# VenturinoDrive.net
KiCad netlist of a schematic drawn in EAGLE
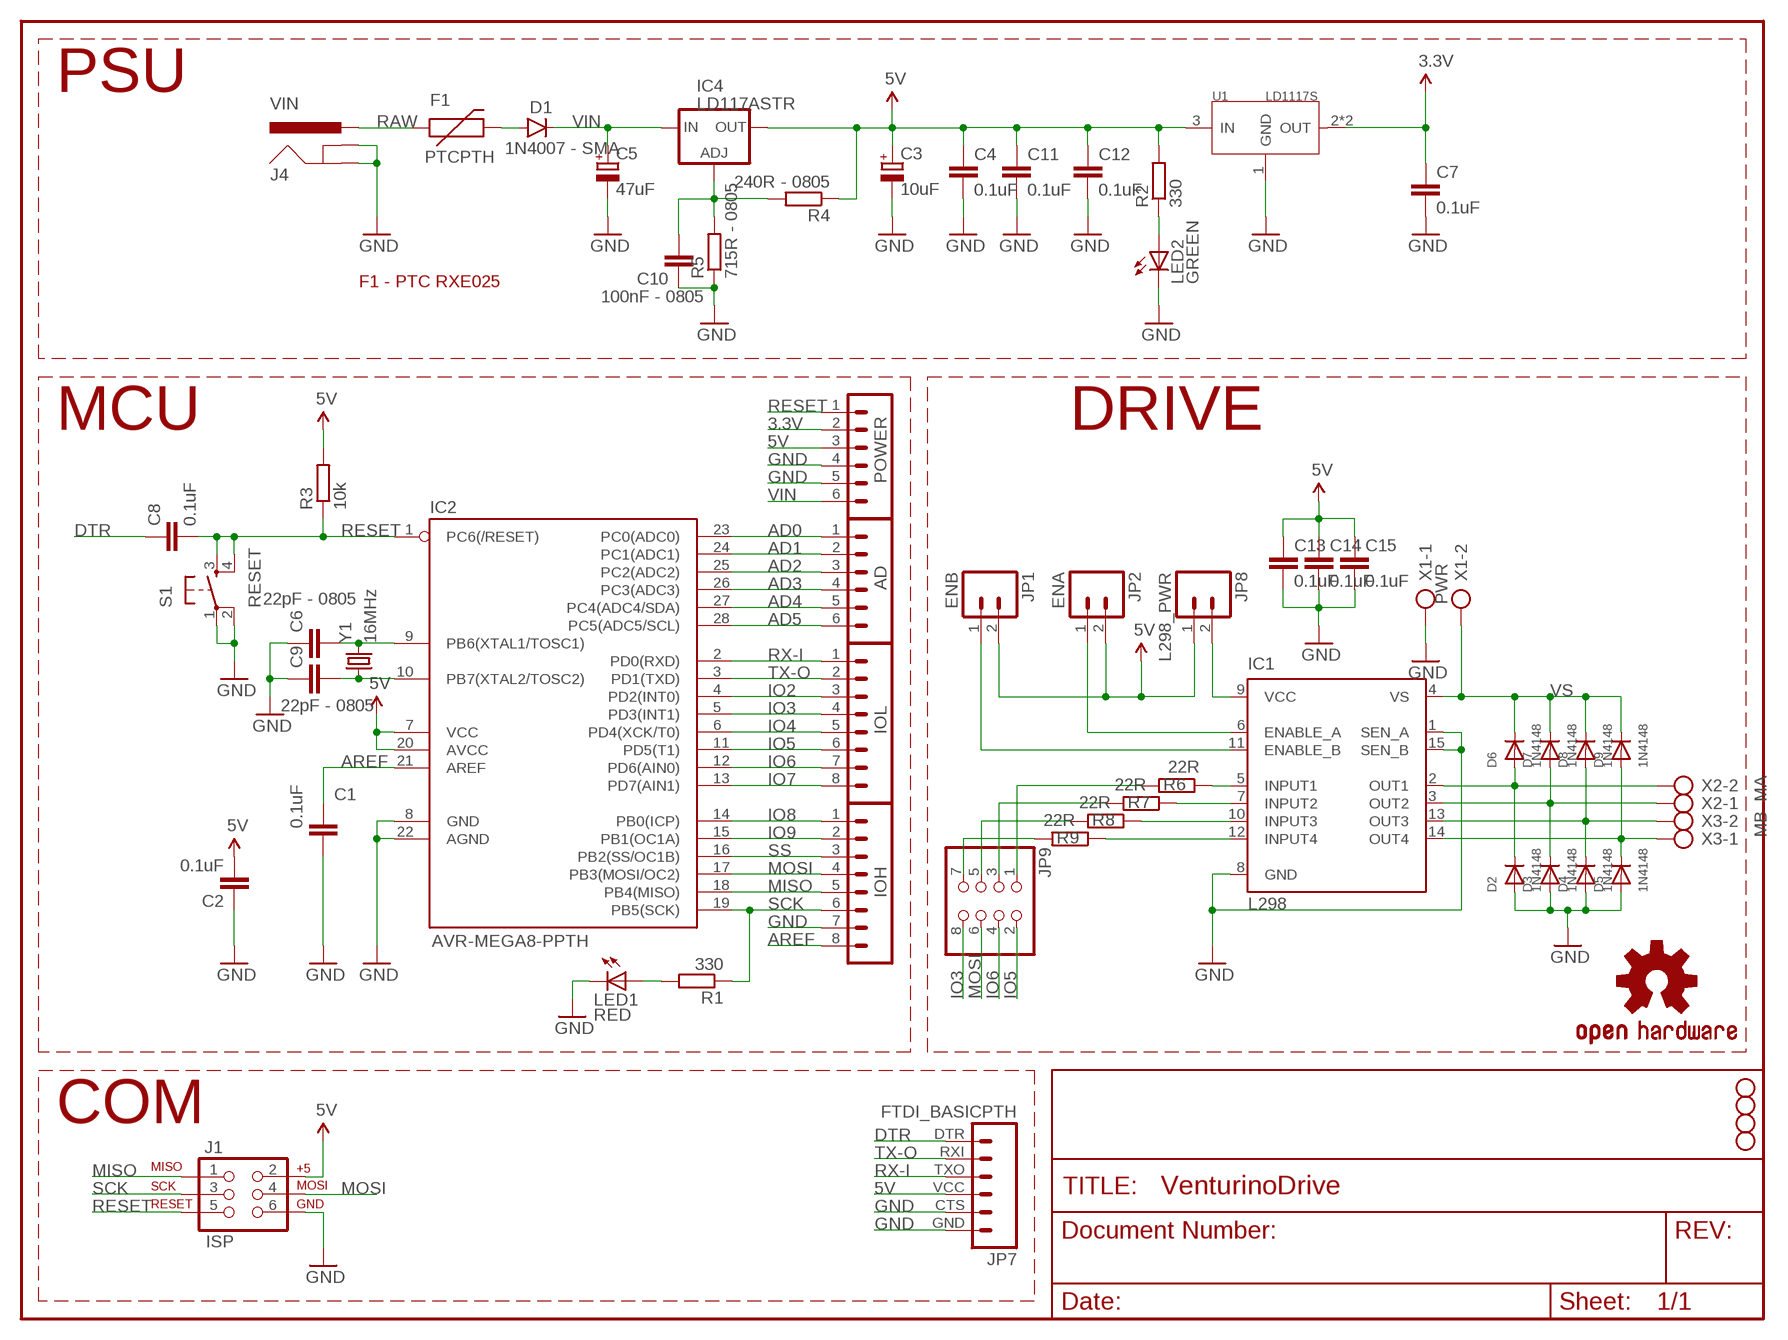
[diagram p0: schematic, sheet 1]

(export (version "E")
  (design (tool "Eeschema 10.0.6"))
  (components
    (comp (ref "AD")
      (value "M06SIP")
      (footprint "eagle-import:1X06")
      (libsource (lib "eagle-import") (part "M06SIP"))
    )
    (comp (ref "C1")
      (value "0.1uF")
      (footprint "eagle-import:C0805")
      (libsource (lib "eagle-import") (part "C-EUC0805"))
    )
    (comp (ref "C2")
      (value "0.1uF")
      (footprint "eagle-import:C0805")
      (libsource (lib "eagle-import") (part "C-EUC0805"))
    )
    (comp (ref "C3")
      (value "10uF")
      (footprint "eagle-import:PANASONIC_B")
      (libsource (lib "eagle-import") (part "CPOL-EUB"))
    )
    (comp (ref "C4")
      (value "0.1uF")
      (footprint "eagle-import:C0805")
      (libsource (lib "eagle-import") (part "C-EUC0805"))
    )
    (comp (ref "C5")
      (value "47uF")
      (footprint "eagle-import:PANASONIC_B")
      (libsource (lib "eagle-import") (part "CPOL-EUB"))
    )
    (comp (ref "C6")
      (value "22pF - 0805")
      (footprint "eagle-import:C0805")
      (libsource (lib "eagle-import") (part "C-EUC0805"))
    )
    (comp (ref "C7")
      (value "0.1uF")
      (footprint "eagle-import:C0805")
      (libsource (lib "eagle-import") (part "C-EUC0805"))
    )
    (comp (ref "C8")
      (value "0.1uF")
      (footprint "eagle-import:C0805")
      (libsource (lib "eagle-import") (part "C-EUC0805"))
    )
    (comp (ref "C9")
      (value "22pF - 0805")
      (footprint "eagle-import:C0805")
      (libsource (lib "eagle-import") (part "C-EUC0805"))
    )
    (comp (ref "C10")
      (value "100nF - 0805")
      (footprint "eagle-import:C0805")
      (libsource (lib "eagle-import") (part "C-EUC0805"))
    )
    (comp (ref "C11")
      (value "0.1uF")
      (footprint "eagle-import:C0805")
      (libsource (lib "eagle-import") (part "C-EUC0805"))
    )
    (comp (ref "C12")
      (value "0.1uF")
      (footprint "eagle-import:C0805")
      (libsource (lib "eagle-import") (part "C-EUC0805"))
    )
    (comp (ref "C13")
      (value "0.1uF")
      (footprint "eagle-import:C0805")
      (libsource (lib "eagle-import") (part "C-EUC0805"))
    )
    (comp (ref "C14")
      (value "0.1uF")
      (footprint "eagle-import:C0805")
      (libsource (lib "eagle-import") (part "C-EUC0805"))
    )
    (comp (ref "C15")
      (value "0.1uF")
      (footprint "eagle-import:C0805")
      (libsource (lib "eagle-import") (part "C-EUC0805"))
    )
    (comp (ref "D1")
      (value "1N4007 - SMA")
      (footprint "eagle-import:SMA-DIODE")
      (libsource (lib "eagle-import") (part "DIODESMA"))
    )
    (comp (ref "D2")
      (value "1N4148")
      (footprint "eagle-import:SMADIODE")
      (libsource (lib "eagle-import") (part "adafruit_DIODESMA"))
    )
    (comp (ref "D3")
      (value "1N4148")
      (footprint "eagle-import:SMADIODE")
      (libsource (lib "eagle-import") (part "adafruit_DIODESMA"))
    )
    (comp (ref "D4")
      (value "1N4148")
      (footprint "eagle-import:SMADIODE")
      (libsource (lib "eagle-import") (part "adafruit_DIODESMA"))
    )
    (comp (ref "D5")
      (value "1N4148")
      (footprint "eagle-import:SMADIODE")
      (libsource (lib "eagle-import") (part "adafruit_DIODESMA"))
    )
    (comp (ref "D6")
      (value "1N4148")
      (footprint "eagle-import:SMADIODE")
      (libsource (lib "eagle-import") (part "adafruit_DIODESMA"))
    )
    (comp (ref "D7")
      (value "1N4148")
      (footprint "eagle-import:SMADIODE")
      (libsource (lib "eagle-import") (part "adafruit_DIODESMA"))
    )
    (comp (ref "D8")
      (value "1N4148")
      (footprint "eagle-import:SMADIODE")
      (libsource (lib "eagle-import") (part "adafruit_DIODESMA"))
    )
    (comp (ref "D9")
      (value "1N4148")
      (footprint "eagle-import:SMADIODE")
      (libsource (lib "eagle-import") (part "adafruit_DIODESMA"))
    )
    (comp (ref "F1")
      (value "PTCPTH")
      (footprint "eagle-import:PTC")
      (libsource (lib "eagle-import") (part "PTCPTH"))
    )
    (comp (ref "IC1")
      (value "L298")
      (footprint "eagle-import:MULTIWATT-15")
      (fields (field (name "MPN") "L298N"))
      (libsource (lib "eagle-import") (part "L298"))
    )
    (comp (ref "IC2")
      (value "AVR-MEGA8-PPTH")
      (footprint "eagle-import:DIL28-3")
      (libsource (lib "eagle-import") (part "AVR-MEGA8-PPTH"))
    )
    (comp (ref "IC4")
      (value "LD117ASTR")
      (footprint "eagle-import:SOT223")
      (libsource (lib "eagle-import") (part "LD117A?STR"))
    )
    (comp (ref "IOH")
      (value "M081X08")
      (footprint "eagle-import:1X08")
      (libsource (lib "eagle-import") (part "M081X08"))
    )
    (comp (ref "IOL")
      (value "M081X08")
      (footprint "eagle-import:1X08")
      (libsource (lib "eagle-import") (part "M081X08"))
    )
    (comp (ref "J1")
      (value "ISP")
      (footprint "eagle-import:2X3")
      (libsource (lib "eagle-import") (part "AVR_SPI_PRG_6PTH"))
    )
    (comp (ref "J4")
      (value "VIN")
      (footprint "eagle-import:POWER_JACK_PTH_LOCK")
      (libsource (lib "eagle-import") (part "POWER_JACKPTH_LOCK"))
    )
    (comp (ref "JP1")
      (value "ENB")
      (footprint "eagle-import:1X02")
      (libsource (lib "eagle-import") (part "M02PTH"))
    )
    (comp (ref "JP2")
      (value "ENA")
      (footprint "eagle-import:1X02")
      (libsource (lib "eagle-import") (part "M02PTH"))
    )
    (comp (ref "JP3")
      (value "STAND-OFF")
      (footprint "eagle-import:STAND-OFF")
      (libsource (lib "eagle-import") (part "STAND-OFF"))
    )
    (comp (ref "JP4")
      (value "STAND-OFF")
      (footprint "eagle-import:STAND-OFF")
      (libsource (lib "eagle-import") (part "STAND-OFF"))
    )
    (comp (ref "JP5")
      (value "STAND-OFF")
      (footprint "eagle-import:STAND-OFF")
      (libsource (lib "eagle-import") (part "STAND-OFF"))
    )
    (comp (ref "JP6")
      (value "STAND-OFF")
      (footprint "eagle-import:STAND-OFF")
      (libsource (lib "eagle-import") (part "STAND-OFF"))
    )
    (comp (ref "JP7")
      (value "FTDI_BASICPTH")
      (footprint "eagle-import:FTDI_BASIC")
      (libsource (lib "eagle-import") (part "FTDI_BASICPTH"))
    )
    (comp (ref "JP8")
      (value "L298_PWR")
      (footprint "eagle-import:1X02")
      (libsource (lib "eagle-import") (part "M02PTH"))
    )
    (comp (ref "JP9")
      (value "PINHD-2X4")
      (footprint "eagle-import:2X04")
      (libsource (lib "eagle-import") (part "PINHD-2X4"))
    )
    (comp (ref "LED1")
      (value "RED")
      (footprint "eagle-import:SML0805")
      (libsource (lib "eagle-import") (part "LEDSML0805"))
    )
    (comp (ref "LED2")
      (value "GREEN")
      (footprint "eagle-import:SML0805")
      (libsource (lib "eagle-import") (part "LEDSML0805"))
    )
    (comp (ref "POWER")
      (value "M06SIP")
      (footprint "eagle-import:1X06")
      (libsource (lib "eagle-import") (part "M06SIP"))
    )
    (comp (ref "R1")
      (value "330")
      (footprint "eagle-import:R0805")
      (libsource (lib "eagle-import") (part "R-EU_R0805"))
    )
    (comp (ref "R2")
      (value "330")
      (footprint "eagle-import:R0805")
      (libsource (lib "eagle-import") (part "R-EU_R0805"))
    )
    (comp (ref "R3")
      (value "10k")
      (footprint "eagle-import:R0805")
      (libsource (lib "eagle-import") (part "R-EU_R0805"))
    )
    (comp (ref "R4")
      (value "240R - 0805")
      (footprint "eagle-import:R0805")
      (libsource (lib "eagle-import") (part "R-EU_R0805"))
    )
    (comp (ref "R5")
      (value "715R - 0805")
      (footprint "eagle-import:R0805")
      (libsource (lib "eagle-import") (part "R-EU_R0805"))
    )
    (comp (ref "R6")
      (value "22R")
      (footprint "eagle-import:R0805")
      (libsource (lib "eagle-import") (part "R-EU_R0805"))
    )
    (comp (ref "R7")
      (value "22R")
      (footprint "eagle-import:R0805")
      (libsource (lib "eagle-import") (part "R-EU_R0805"))
    )
    (comp (ref "R8")
      (value "22R")
      (footprint "eagle-import:R0805")
      (libsource (lib "eagle-import") (part "R-EU_R0805"))
    )
    (comp (ref "R9")
      (value "22R")
      (footprint "eagle-import:R0805")
      (libsource (lib "eagle-import") (part "R-EU_R0805"))
    )
    (comp (ref "S1")
      (value "RESET")
      (footprint "eagle-import:TACTILE-PTH")
      (libsource (lib "eagle-import") (part "TAC_SWITCHPTH"))
    )
    (comp (ref "U$7")
      (value "OSHW-LOGOM")
      (footprint "eagle-import:OSHW-LOGO-M")
      (libsource (lib "eagle-import") (part "OSHW-LOGOM"))
    )
    (comp (ref "U1")
      (value "LD1117S")
      (footprint "eagle-import:SOT-223")
      (libsource (lib "eagle-import") (part "LD1117S"))
    )
    (comp (ref "X1")
      (value "PWR")
      (footprint "eagle-import:AK500_2")
      (libsource (lib "eagle-import") (part "AK500/2"))
    )
    (comp (ref "X2")
      (value "MA")
      (footprint "eagle-import:AK500_2")
      (libsource (lib "eagle-import") (part "AK500/2"))
    )
    (comp (ref "X3")
      (value "MB")
      (footprint "eagle-import:AK500_2")
      (libsource (lib "eagle-import") (part "AK500/2"))
    )
    (comp (ref "Y1")
      (value "16MHz")
      (footprint "eagle-import:HC49US")
      (libsource (lib "eagle-import") (part "CRYSTALHC49US"))
    )
  )
  (nets
    (net (code "1") (name "/AD0") (class "Default")
      (node (ref "AD") (pin "1") (pinfunction "1_1") (pintype "passive"))
      (node (ref "IC2") (pin "23") (pinfunction "PC0(ADC0)_23") (pintype "bidirectional"))
    )
    (net (code "2") (name "/AD1") (class "Default")
      (node (ref "AD") (pin "2") (pinfunction "2_2") (pintype "passive"))
      (node (ref "IC2") (pin "24") (pinfunction "PC1(ADC1)_24") (pintype "bidirectional"))
    )
    (net (code "3") (name "/AD2") (class "Default")
      (node (ref "AD") (pin "3") (pinfunction "3_3") (pintype "passive"))
      (node (ref "IC2") (pin "25") (pinfunction "PC2(ADC2)_25") (pintype "bidirectional"))
    )
    (net (code "4") (name "/AD3") (class "Default")
      (node (ref "AD") (pin "4") (pinfunction "4_4") (pintype "passive"))
      (node (ref "IC2") (pin "26") (pinfunction "PC3(ADC3)_26") (pintype "bidirectional"))
    )
    (net (code "5") (name "/AD4") (class "Default")
      (node (ref "AD") (pin "5") (pinfunction "5_5") (pintype "passive"))
      (node (ref "IC2") (pin "27") (pinfunction "PC4(ADC4/SDA)_27") (pintype "bidirectional"))
    )
    (net (code "6") (name "/AD5") (class "Default")
      (node (ref "AD") (pin "6") (pinfunction "6_6") (pintype "passive"))
      (node (ref "IC2") (pin "28") (pinfunction "PC5(ADC5/SCL)_28") (pintype "bidirectional"))
    )
    (net (code "7") (name "/AREF") (class "Default")
      (node (ref "C1") (pin "1") (pinfunction "1_1") (pintype "passive"))
      (node (ref "IC2") (pin "21") (pinfunction "AREF_21") (pintype "bidirectional"))
      (node (ref "IOH") (pin "8") (pinfunction "8_8") (pintype "passive"))
    )
    (net (code "8") (name "/DTR") (class "Default")
      (node (ref "C8") (pin "1") (pinfunction "1_1") (pintype "passive"))
      (node (ref "JP7") (pin "DTR") (pinfunction "1_DTR") (pintype "passive"))
    )
    (net (code "9") (name "/IO2") (class "Default")
      (node (ref "IC2") (pin "4") (pinfunction "PD2(INT0)_4") (pintype "bidirectional"))
      (node (ref "IOL") (pin "3") (pinfunction "3_3") (pintype "passive"))
    )
    (net (code "10") (name "/IO3") (class "Default")
      (node (ref "IC2") (pin "5") (pinfunction "PD3(INT1)_5") (pintype "bidirectional"))
      (node (ref "IOL") (pin "4") (pinfunction "4_4") (pintype "passive"))
      (node (ref "JP9") (pin "8") (pinfunction "8_8") (pintype "passive"))
    )
    (net (code "11") (name "/IO4") (class "Default")
      (node (ref "IC2") (pin "6") (pinfunction "PD4(XCK/T0)_6") (pintype "bidirectional"))
      (node (ref "IOL") (pin "5") (pinfunction "5_5") (pintype "passive"))
    )
    (net (code "12") (name "/IO5") (class "Default")
      (node (ref "IC2") (pin "11") (pinfunction "PD5(T1)_11") (pintype "bidirectional"))
      (node (ref "IOL") (pin "6") (pinfunction "6_6") (pintype "passive"))
      (node (ref "JP9") (pin "2") (pinfunction "2_2") (pintype "passive"))
    )
    (net (code "13") (name "/IO6") (class "Default")
      (node (ref "IC2") (pin "12") (pinfunction "PD6(AIN0)_12") (pintype "bidirectional"))
      (node (ref "IOL") (pin "7") (pinfunction "7_7") (pintype "passive"))
      (node (ref "JP9") (pin "4") (pinfunction "4_4") (pintype "passive"))
    )
    (net (code "14") (name "/IO7") (class "Default")
      (node (ref "IC2") (pin "13") (pinfunction "PD7(AIN1)_13") (pintype "bidirectional"))
      (node (ref "IOL") (pin "8") (pinfunction "8_8") (pintype "passive"))
    )
    (net (code "15") (name "/IO8") (class "Default")
      (node (ref "IC2") (pin "14") (pinfunction "PB0(ICP)_14") (pintype "bidirectional"))
      (node (ref "IOH") (pin "1") (pinfunction "1_1") (pintype "passive"))
    )
    (net (code "16") (name "/IO9") (class "Default")
      (node (ref "IC2") (pin "15") (pinfunction "PB1(OC1A)_15") (pintype "bidirectional"))
      (node (ref "IOH") (pin "2") (pinfunction "2_2") (pintype "passive"))
    )
    (net (code "17") (name "/MISO") (class "Default")
      (node (ref "IC2") (pin "18") (pinfunction "PB4(MISO)_18") (pintype "bidirectional"))
      (node (ref "IOH") (pin "5") (pinfunction "5_5") (pintype "passive"))
      (node (ref "J1") (pin "1") (pinfunction "1_1") (pintype "passive"))
    )
    (net (code "18") (name "/MOSI") (class "Default")
      (node (ref "IC2") (pin "17") (pinfunction "PB3(MOSI/OC2)_17") (pintype "bidirectional"))
      (node (ref "IOH") (pin "4") (pinfunction "4_4") (pintype "passive"))
      (node (ref "J1") (pin "4") (pinfunction "4_4") (pintype "passive"))
      (node (ref "JP9") (pin "6") (pinfunction "6_6") (pintype "passive"))
    )
    (net (code "19") (name "/RAW") (class "Default")
      (node (ref "F1") (pin "P$1") (pinfunction "1_P$1") (pintype "bidirectional"))
      (node (ref "J4") (pin "PWR") (pinfunction "PWR_PWR") (pintype "bidirectional"))
    )
    (net (code "20") (name "/RESET") (class "Default")
      (node (ref "C8") (pin "2") (pinfunction "2_2") (pintype "passive"))
      (node (ref "IC2") (pin "1") (pinfunction "PC6(/RESET)_1") (pintype "bidirectional"))
      (node (ref "J1") (pin "5") (pinfunction "5_5") (pintype "passive"))
      (node (ref "POWER") (pin "1") (pinfunction "1_1") (pintype "passive"))
      (node (ref "R3") (pin "1") (pinfunction "1_1") (pintype "passive"))
      (node (ref "S1") (pin "3") (pinfunction "3_3") (pintype "passive"))
      (node (ref "S1") (pin "4") (pinfunction "4_4") (pintype "passive"))
    )
    (net (code "21") (name "/RX-I") (class "Default")
      (node (ref "IC2") (pin "2") (pinfunction "PD0(RXD)_2") (pintype "bidirectional"))
      (node (ref "IOL") (pin "1") (pinfunction "1_1") (pintype "passive"))
      (node (ref "JP7") (pin "TXO") (pinfunction "3_TXO") (pintype "passive"))
    )
    (net (code "22") (name "/SCK") (class "Default")
      (node (ref "IC2") (pin "19") (pinfunction "PB5(SCK)_19") (pintype "bidirectional"))
      (node (ref "IOH") (pin "6") (pinfunction "6_6") (pintype "passive"))
      (node (ref "J1") (pin "3") (pinfunction "3_3") (pintype "passive"))
      (node (ref "R1") (pin "1") (pinfunction "1_1") (pintype "passive"))
    )
    (net (code "23") (name "/SS") (class "Default")
      (node (ref "IC2") (pin "16") (pinfunction "PB2(SS/OC1B)_16") (pintype "bidirectional"))
      (node (ref "IOH") (pin "3") (pinfunction "3_3") (pintype "passive"))
    )
    (net (code "24") (name "/TX-O") (class "Default")
      (node (ref "IC2") (pin "3") (pinfunction "PD1(TXD)_3") (pintype "bidirectional"))
      (node (ref "IOL") (pin "2") (pinfunction "2_2") (pintype "passive"))
      (node (ref "JP7") (pin "RXI") (pinfunction "2_RXI") (pintype "passive"))
    )
    (net (code "25") (name "/VIN") (class "Default")
      (node (ref "C5") (pin "+") (pinfunction "+_+") (pintype "passive"))
      (node (ref "D1") (pin "C") (pinfunction "C_C") (pintype "passive"))
      (node (ref "IC4") (pin "3") (pinfunction "IN_3") (pintype "input"))
      (node (ref "POWER") (pin "6") (pinfunction "6_6") (pintype "passive"))
    )
    (net (code "26") (name "/VS") (class "Default")
      (node (ref "D6") (pin "C") (pinfunction "C_C") (pintype "passive"))
      (node (ref "D7") (pin "C") (pinfunction "C_C") (pintype "passive"))
      (node (ref "D8") (pin "C") (pinfunction "C_C") (pintype "passive"))
      (node (ref "D9") (pin "C") (pinfunction "C_C") (pintype "passive"))
      (node (ref "IC1") (pin "4") (pinfunction "VS_4") (pintype "power_in"))
      (node (ref "X1") (pin "2") (pinfunction "KL_2") (pintype "passive"))
    )
    (net (code "27") (name "3.3V") (class "Default")
      (node (ref "C7") (pin "1") (pinfunction "1_1") (pintype "passive"))
      (node (ref "POWER") (pin "2") (pinfunction "2_2") (pintype "passive"))
      (node (ref "U1") (pin "2") (pinfunction "OUT_2") (pintype "bidirectional"))
      (node (ref "U1") (pin "TER") (pinfunction "OUT_TER") (pintype "bidirectional"))
    )
    (net (code "28") (name "5V") (class "Default")
      (node (ref "C11") (pin "1") (pinfunction "1_1") (pintype "passive"))
      (node (ref "C12") (pin "1") (pinfunction "1_1") (pintype "passive"))
      (node (ref "C13") (pin "1") (pinfunction "1_1") (pintype "passive"))
      (node (ref "C14") (pin "1") (pinfunction "1_1") (pintype "passive"))
      (node (ref "C15") (pin "1") (pinfunction "1_1") (pintype "passive"))
      (node (ref "C2") (pin "2") (pinfunction "2_2") (pintype "passive"))
      (node (ref "C3") (pin "+") (pinfunction "+_+") (pintype "passive"))
      (node (ref "C4") (pin "1") (pinfunction "1_1") (pintype "passive"))
      (node (ref "IC2") (pin "20") (pinfunction "AVCC_20") (pintype "bidirectional"))
      (node (ref "IC2") (pin "7") (pinfunction "VCC_7") (pintype "bidirectional"))
      (node (ref "IC4") (pin "4") (pinfunction "OUT_4") (pintype "passive"))
      (node (ref "J1") (pin "2") (pinfunction "2_2") (pintype "passive"))
      (node (ref "JP1") (pin "2") (pinfunction "2_2") (pintype "passive"))
      (node (ref "JP2") (pin "2") (pinfunction "2_2") (pintype "passive"))
      (node (ref "JP7") (pin "VCC") (pinfunction "4_VCC") (pintype "passive"))
      (node (ref "JP8") (pin "1") (pinfunction "1_1") (pintype "passive"))
      (node (ref "POWER") (pin "3") (pinfunction "3_3") (pintype "passive"))
      (node (ref "R2") (pin "2") (pinfunction "2_2") (pintype "passive"))
      (node (ref "R3") (pin "2") (pinfunction "2_2") (pintype "passive"))
      (node (ref "R4") (pin "1") (pinfunction "1_1") (pintype "passive"))
      (node (ref "U1") (pin "3") (pinfunction "IN_3") (pintype "bidirectional"))
    )
    (net (code "29") (name "GND") (class "Default")
      (node (ref "C1") (pin "2") (pinfunction "2_2") (pintype "passive"))
      (node (ref "C10") (pin "1") (pinfunction "1_1") (pintype "passive"))
      (node (ref "C11") (pin "2") (pinfunction "2_2") (pintype "passive"))
      (node (ref "C12") (pin "2") (pinfunction "2_2") (pintype "passive"))
      (node (ref "C13") (pin "2") (pinfunction "2_2") (pintype "passive"))
      (node (ref "C14") (pin "2") (pinfunction "2_2") (pintype "passive"))
      (node (ref "C15") (pin "2") (pinfunction "2_2") (pintype "passive"))
      (node (ref "C2") (pin "1") (pinfunction "1_1") (pintype "passive"))
      (node (ref "C3") (pin "-") (pinfunction "-_-") (pintype "passive"))
      (node (ref "C4") (pin "2") (pinfunction "2_2") (pintype "passive"))
      (node (ref "C5") (pin "-") (pinfunction "-_-") (pintype "passive"))
      (node (ref "C6") (pin "1") (pinfunction "1_1") (pintype "passive"))
      (node (ref "C7") (pin "2") (pinfunction "2_2") (pintype "passive"))
      (node (ref "C9") (pin "1") (pinfunction "1_1") (pintype "passive"))
      (node (ref "D2") (pin "A") (pinfunction "A_A") (pintype "passive"))
      (node (ref "D3") (pin "A") (pinfunction "A_A") (pintype "passive"))
      (node (ref "D4") (pin "A") (pinfunction "A_A") (pintype "passive"))
      (node (ref "D5") (pin "A") (pinfunction "A_A") (pintype "passive"))
      (node (ref "IC1") (pin "1") (pinfunction "SEN_A_1") (pintype "input"))
      (node (ref "IC1") (pin "15") (pinfunction "SEN_B_15") (pintype "input"))
      (node (ref "IC1") (pin "8") (pinfunction "GND_8") (pintype "power_in"))
      (node (ref "IC2") (pin "22") (pinfunction "AGND_22") (pintype "bidirectional"))
      (node (ref "IC2") (pin "8") (pinfunction "GND_8") (pintype "bidirectional"))
      (node (ref "IOH") (pin "7") (pinfunction "7_7") (pintype "passive"))
      (node (ref "J1") (pin "6") (pinfunction "6_6") (pintype "passive"))
      (node (ref "J4") (pin "GND") (pinfunction "GND_GND") (pintype "bidirectional"))
      (node (ref "J4") (pin "GNDBREAK") (pinfunction "GNDBREAK_GNDBREAK") (pintype "bidirectional"))
      (node (ref "JP7") (pin "CTS") (pinfunction "5_CTS") (pintype "passive"))
      (node (ref "JP7") (pin "GND") (pinfunction "6_GND") (pintype "passive"))
      (node (ref "LED1") (pin "C") (pinfunction "C_C") (pintype "passive"))
      (node (ref "LED2") (pin "C") (pinfunction "C_C") (pintype "passive"))
      (node (ref "POWER") (pin "4") (pinfunction "4_4") (pintype "passive"))
      (node (ref "POWER") (pin "5") (pinfunction "5_5") (pintype "passive"))
      (node (ref "R5") (pin "1") (pinfunction "1_1") (pintype "passive"))
      (node (ref "S1") (pin "1") (pinfunction "1_1") (pintype "passive"))
      (node (ref "S1") (pin "2") (pinfunction "2_2") (pintype "passive"))
      (node (ref "U1") (pin "1") (pinfunction "GND_1") (pintype "bidirectional"))
      (node (ref "X1") (pin "1") (pinfunction "KL_1") (pintype "passive"))
    )
    (net (code "30") (name "Net-(F1-2)") (class "Default")
      (node (ref "D1") (pin "A") (pinfunction "A_A") (pintype "passive"))
      (node (ref "F1") (pin "P$2") (pinfunction "2_P$2") (pintype "bidirectional"))
    )
    (net (code "31") (name "Net-(IC1-ENABLE_A)") (class "Default")
      (node (ref "IC1") (pin "6") (pinfunction "ENABLE_A_6") (pintype "input"))
      (node (ref "JP2") (pin "1") (pinfunction "1_1") (pintype "passive"))
    )
    (net (code "32") (name "Net-(IC1-ENABLE_B)") (class "Default")
      (node (ref "IC1") (pin "11") (pinfunction "ENABLE_B_11") (pintype "input"))
      (node (ref "JP1") (pin "1") (pinfunction "1_1") (pintype "passive"))
    )
    (net (code "33") (name "Net-(IC1-INPUT1)") (class "Default")
      (node (ref "IC1") (pin "5") (pinfunction "INPUT1_5") (pintype "input"))
      (node (ref "R6") (pin "1") (pinfunction "1_1") (pintype "passive"))
    )
    (net (code "34") (name "Net-(IC1-INPUT2)") (class "Default")
      (node (ref "IC1") (pin "7") (pinfunction "INPUT2_7") (pintype "input"))
      (node (ref "R7") (pin "1") (pinfunction "1_1") (pintype "passive"))
    )
    (net (code "35") (name "Net-(IC1-INPUT3)") (class "Default")
      (node (ref "IC1") (pin "10") (pinfunction "INPUT3_10") (pintype "input"))
      (node (ref "R8") (pin "1") (pinfunction "1_1") (pintype "passive"))
    )
    (net (code "36") (name "Net-(IC1-INPUT4)") (class "Default")
      (node (ref "IC1") (pin "12") (pinfunction "INPUT4_12") (pintype "input"))
      (node (ref "R9") (pin "1") (pinfunction "1_1") (pintype "passive"))
    )
    (net (code "37") (name "Net-(IC1-OUT1)") (class "Default")
      (node (ref "D2") (pin "C") (pinfunction "C_C") (pintype "passive"))
      (node (ref "D6") (pin "A") (pinfunction "A_A") (pintype "passive"))
      (node (ref "IC1") (pin "2") (pinfunction "OUT1_2") (pintype "output"))
      (node (ref "X2") (pin "2") (pinfunction "KL_2") (pintype "passive"))
    )
    (net (code "38") (name "Net-(IC1-OUT2)") (class "Default")
      (node (ref "D3") (pin "C") (pinfunction "C_C") (pintype "passive"))
      (node (ref "D7") (pin "A") (pinfunction "A_A") (pintype "passive"))
      (node (ref "IC1") (pin "3") (pinfunction "OUT2_3") (pintype "output"))
      (node (ref "X2") (pin "1") (pinfunction "KL_1") (pintype "passive"))
    )
    (net (code "39") (name "Net-(IC1-OUT3)") (class "Default")
      (node (ref "D4") (pin "C") (pinfunction "C_C") (pintype "passive"))
      (node (ref "D8") (pin "A") (pinfunction "A_A") (pintype "passive"))
      (node (ref "IC1") (pin "13") (pinfunction "OUT3_13") (pintype "output"))
      (node (ref "X3") (pin "2") (pinfunction "KL_2") (pintype "passive"))
    )
    (net (code "40") (name "Net-(IC1-OUT4)") (class "Default")
      (node (ref "D5") (pin "C") (pinfunction "C_C") (pintype "passive"))
      (node (ref "D9") (pin "A") (pinfunction "A_A") (pintype "passive"))
      (node (ref "IC1") (pin "14") (pinfunction "OUT4_14") (pintype "output"))
      (node (ref "X3") (pin "1") (pinfunction "KL_1") (pintype "passive"))
    )
    (net (code "41") (name "Net-(IC1-VCC)") (class "Default")
      (node (ref "IC1") (pin "9") (pinfunction "VCC_9") (pintype "power_in"))
      (node (ref "JP8") (pin "2") (pinfunction "2_2") (pintype "passive"))
    )
    (net (code "42") (name "Net-(IC2-PB6(XTAL1{slash}TOSC1))") (class "Default")
      (node (ref "C6") (pin "2") (pinfunction "2_2") (pintype "passive"))
      (node (ref "IC2") (pin "9") (pinfunction "PB6(XTAL1/TOSC1)_9") (pintype "bidirectional"))
      (node (ref "Y1") (pin "2") (pinfunction "2_2") (pintype "passive"))
    )
    (net (code "43") (name "Net-(IC2-PB7(XTAL2{slash}TOSC2))") (class "Default")
      (node (ref "C9") (pin "2") (pinfunction "2_2") (pintype "passive"))
      (node (ref "IC2") (pin "10") (pinfunction "PB7(XTAL2/TOSC2)_10") (pintype "bidirectional"))
      (node (ref "Y1") (pin "1") (pinfunction "1_1") (pintype "passive"))
    )
    (net (code "44") (name "Net-(IC4-ADJ)") (class "Default")
      (node (ref "C10") (pin "2") (pinfunction "2_2") (pintype "passive"))
      (node (ref "IC4") (pin "1") (pinfunction "ADJ_1") (pintype "input"))
      (node (ref "R4") (pin "2") (pinfunction "2_2") (pintype "passive"))
      (node (ref "R5") (pin "2") (pinfunction "2_2") (pintype "passive"))
    )
    (net (code "45") (name "Net-(JP9-Pad1)") (class "Default")
      (node (ref "JP9") (pin "1") (pinfunction "1_1") (pintype "passive"))
      (node (ref "R6") (pin "2") (pinfunction "2_2") (pintype "passive"))
    )
    (net (code "46") (name "Net-(JP9-Pad3)") (class "Default")
      (node (ref "JP9") (pin "3") (pinfunction "3_3") (pintype "passive"))
      (node (ref "R7") (pin "2") (pinfunction "2_2") (pintype "passive"))
    )
    (net (code "47") (name "Net-(JP9-Pad5)") (class "Default")
      (node (ref "JP9") (pin "5") (pinfunction "5_5") (pintype "passive"))
      (node (ref "R8") (pin "2") (pinfunction "2_2") (pintype "passive"))
    )
    (net (code "48") (name "Net-(JP9-Pad7)") (class "Default")
      (node (ref "JP9") (pin "7") (pinfunction "7_7") (pintype "passive"))
      (node (ref "R9") (pin "2") (pinfunction "2_2") (pintype "passive"))
    )
    (net (code "49") (name "Net-(LED1-PadA)") (class "Default")
      (node (ref "LED1") (pin "A") (pinfunction "A_A") (pintype "passive"))
      (node (ref "R1") (pin "2") (pinfunction "2_2") (pintype "passive"))
    )
    (net (code "50") (name "Net-(LED2-PadA)") (class "Default")
      (node (ref "LED2") (pin "A") (pinfunction "A_A") (pintype "passive"))
      (node (ref "R2") (pin "1") (pinfunction "1_1") (pintype "passive"))
    )
  )
)
